# Power_Supplies.net
KiCad netlist of a schematic drawn in Altium Designer
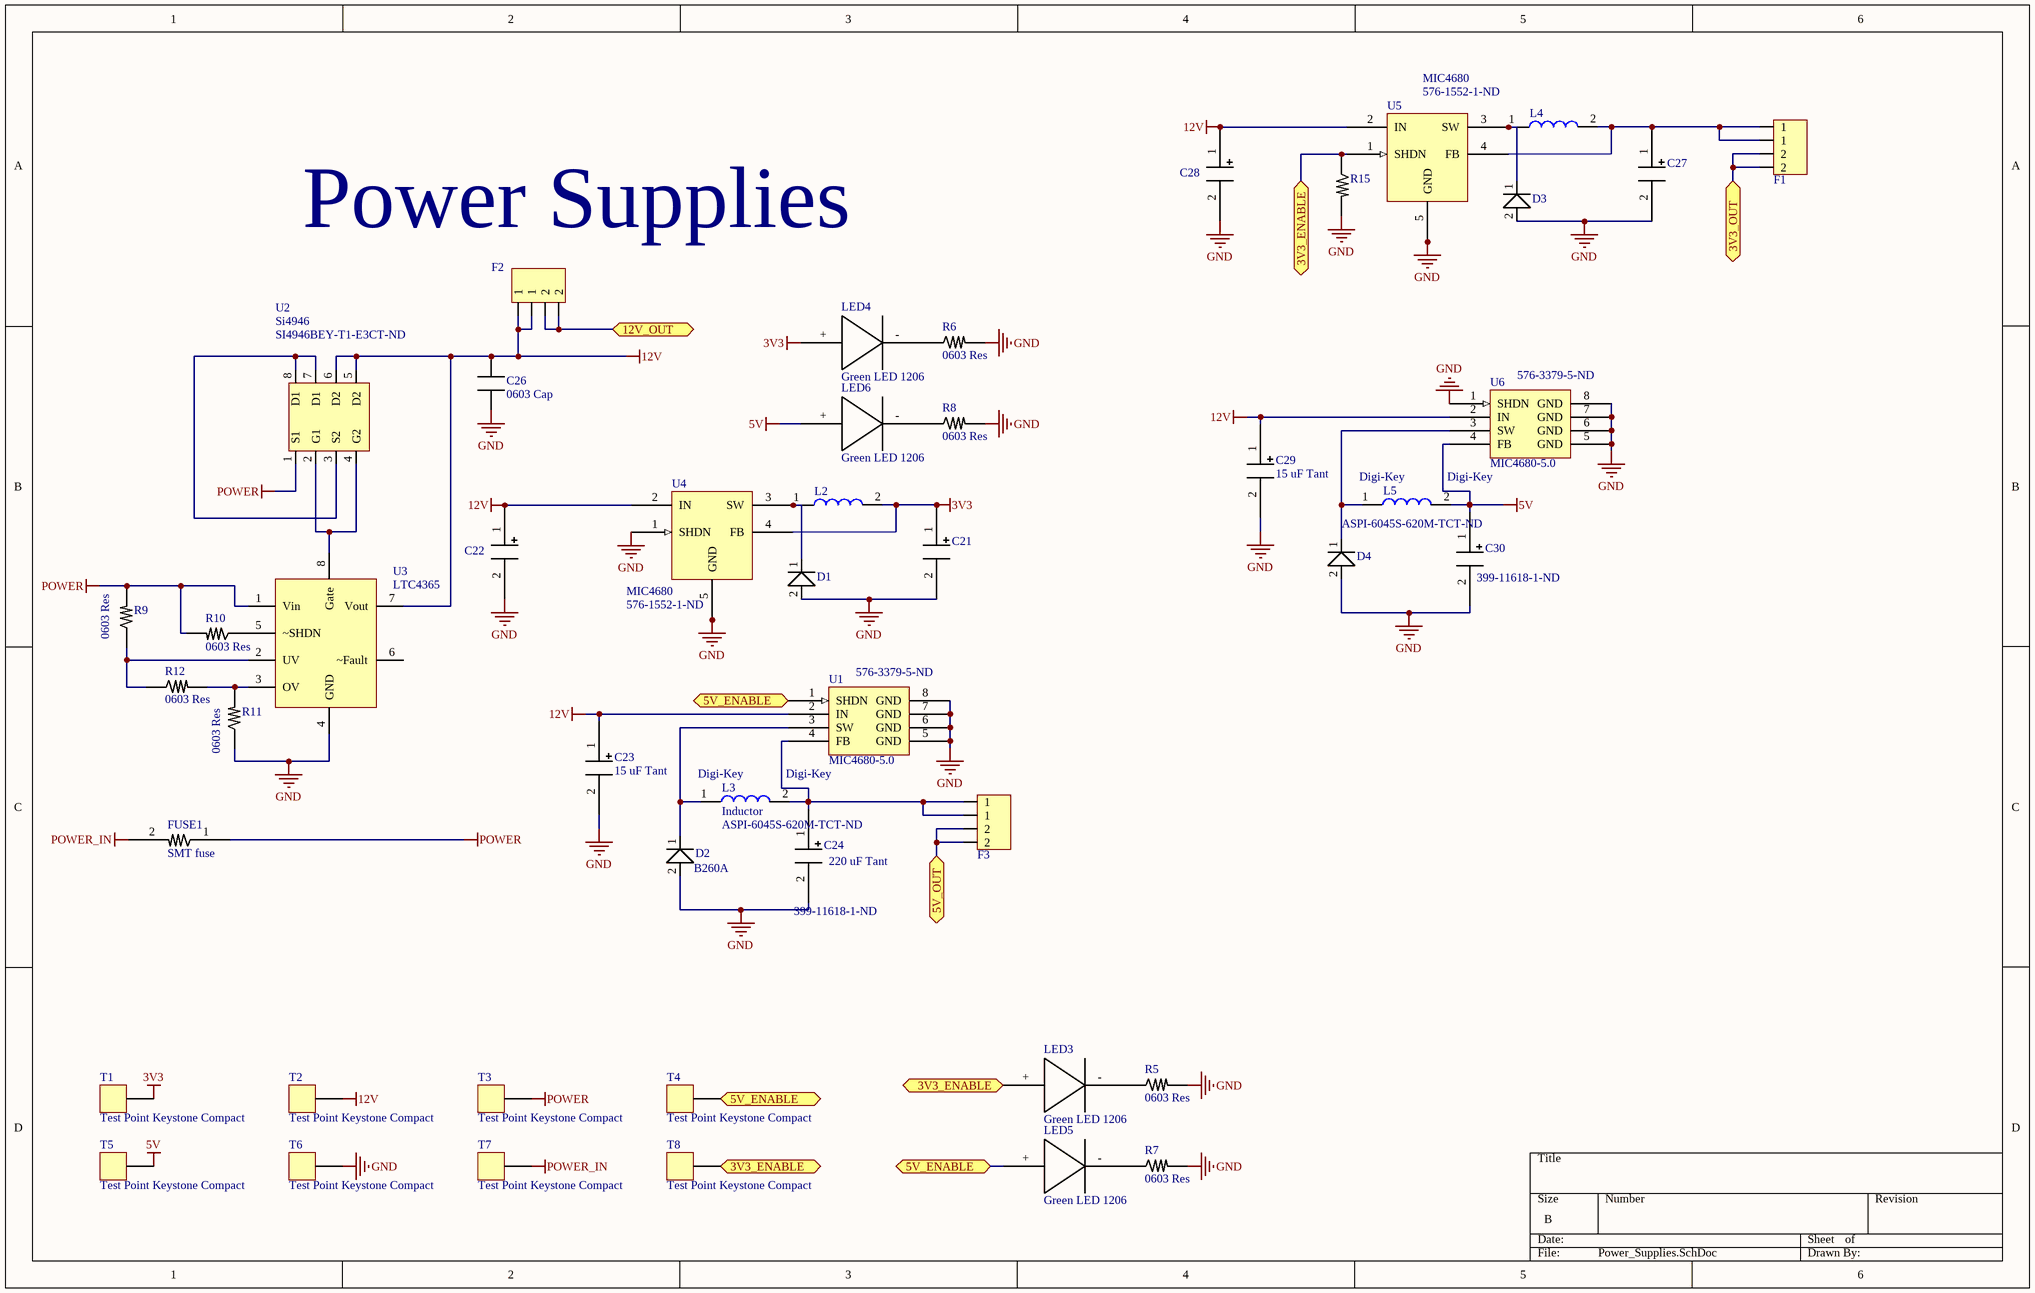
[diagram p0: Power_Supplies.SchDoc]

(export (version "E")
  (design (tool "Eeschema 10.0.6"))
  (components
    (comp (ref "C21")
      (value "220 uF Tantalum Capacitor")
      (footprint "2312 Surface Mount (POLAR)")
      (description "2312 Surface Mount Capacitor")
      (libsource (lib "CUBAJA") (part "220 uF Tantalum Capacitor"))
    )
    (comp (ref "C22")
      (value "15 uF Tantalum Capacitor")
      (footprint "1206 (POLAR)")
      (description "1206 Surface Mount Capacitor")
      (libsource (lib "CUBAJA") (part "15 uF Tantalum Capacitor"))
    )
    (comp (ref "C23")
      (value "15 uF Tant")
      (footprint "1206 (POLAR)")
      (description "1206 Surface Mount Capacitor")
      (libsource (lib "capacitors") (part "15 uF Tantalum Capacitor"))
    )
    (comp (ref "C24")
      (value "220 uF Tant")
      (footprint "2312 Surface Mount (POLAR)")
      (description "2312 Surface Mount Capacitor")
      (fields (field (name "SUPPLIER PART NUMBER 1") "399-11618-1-ND"))
      (libsource (lib "capacitors") (part "220 uF Tantalum Capacitor"))
    )
    (comp (ref "C26")
      (value "0603 Cap")
      (footprint "0603/1608 SMD Resistor")
      (description "100 uF electrolytic cap")
      (libsource (lib "BajaIntegrated") (part "0603 Cap"))
    )
    (comp (ref "C27")
      (value "220 uF Tantalum Capacitor")
      (footprint "2312 Surface Mount (POLAR)")
      (description "2312 Surface Mount Capacitor")
      (libsource (lib "CUBAJA") (part "220 uF Tantalum Capacitor"))
    )
    (comp (ref "C28")
      (value "15 uF Tantalum Capacitor")
      (footprint "1206 (POLAR)")
      (description "1206 Surface Mount Capacitor")
      (libsource (lib "CUBAJA") (part "15 uF Tantalum Capacitor"))
    )
    (comp (ref "C29")
      (value "15 uF Tant")
      (footprint "1206 (POLAR)")
      (description "1206 Surface Mount Capacitor")
      (libsource (lib "capacitors") (part "15 uF Tantalum Capacitor"))
    )
    (comp (ref "C30")
      (value "220 uF Tant")
      (footprint "2312 Surface Mount (POLAR)")
      (description "2312 Surface Mount Capacitor")
      (fields (field (name "SUPPLIER PART NUMBER 1") "399-11618-1-ND"))
      (libsource (lib "capacitors") (part "220 uF Tantalum Capacitor"))
    )
    (comp (ref "D1")
      (value "B260A Flyback Diode")
      (footprint "DO-214AC")
      (libsource (lib "CUBAJA") (part "B260A Flyback Diode"))
    )
    (comp (ref "D2")
      (value "B260A")
      (footprint "DO-214AC")
      (libsource (lib "schottky") (part "B260A Flyback Diode"))
    )
    (comp (ref "D3")
      (value "B260A Flyback Diode")
      (footprint "DO-214AC")
      (libsource (lib "CUBAJA") (part "B260A Flyback Diode"))
    )
    (comp (ref "D4")
      (value "B260A")
      (footprint "DO-214AC")
      (libsource (lib "schottky") (part "B260A Flyback Diode"))
    )
    (comp (ref "F1")
      (value "Keystone Fuseholder")
      (footprint "Keystone Fuseholder 3568")
      (libsource (lib "CornellBajaLibrary") (part "Keystone Fuseholder"))
    )
    (comp (ref "F2")
      (value "Keystone Fuseholder")
      (footprint "Keystone Fuseholder 3568")
      (libsource (lib "") (part "Keystone Fuseholder_1"))
    )
    (comp (ref "F3")
      (value "Keystone Fuseholder")
      (footprint "Keystone Fuseholder 3568")
      (libsource (lib "CornellBajaLibrary") (part "Keystone Fuseholder"))
    )
    (comp (ref "FUSE1")
      (value "SMT fuse")
      (footprint "1206")
      (description "0 ohm surface mount resistor.")
      (libsource (lib "Integrated_Library") (part "0 Resistor Surface mount 1206"))
    )
    (comp (ref "L2")
      (value "ASPI-6045S")
      (footprint "ASPI-6045")
      (description "68 uH 1.2A surface mount inductor")
      (libsource (lib "CUBAJA") (part "ASPI-6045S"))
    )
    (comp (ref "L3")
      (value "Inductor")
      (footprint "ASPI-6045")
      (fields
        (field (name "SUPPLIER 1") "Digi-Key")
        (field (name "SUPPLIER PART NUMBER 1") "ASPI-6045S-620M-TCT-ND")
      )
      (libsource (lib "CornellBajaLibrary") (part "Inductor"))
    )
    (comp (ref "L4")
      (value "ASPI-6045S")
      (footprint "ASPI-6045")
      (description "68 uH 1.2A surface mount inductor")
      (libsource (lib "CUBAJA") (part "ASPI-6045S"))
    )
    (comp (ref "L5")
      (value "Inductor")
      (footprint "ASPI-6045")
      (fields
        (field (name "SUPPLIER 1") "Digi-Key")
        (field (name "SUPPLIER PART NUMBER 1") "ASPI-6045S-620M-TCT-ND")
      )
      (libsource (lib "CornellBajaLibrary") (part "Inductor"))
    )
    (comp (ref "LED3")
      (value "Green LED 1206")
      (footprint "Panel_Mount_LED")
      (description "Green surface mount LED")
      (libsource (lib "CUBAJA") (part "1206 Green LED"))
    )
    (comp (ref "LED4")
      (value "Green LED 1206")
      (footprint "Panel_Mount_LED")
      (description "Green surface mount LED")
      (libsource (lib "CUBAJA") (part "1206 Green LED"))
    )
    (comp (ref "LED5")
      (value "Green LED 1206")
      (footprint "Cathode Mark 1206 led footprint")
      (description "Green surface mount LED")
      (libsource (lib "CUBAJA") (part "1206 Green LED"))
    )
    (comp (ref "LED6")
      (value "Green LED 1206")
      (footprint "Cathode Mark 1206 led footprint")
      (description "Green surface mount LED")
      (libsource (lib "CUBAJA") (part "1206 Green LED"))
    )
    (comp (ref "R5")
      (value "0603 Res")
      (footprint "0603/1608 SMD Resistor")
      (libsource (lib "CornellBajaLibrary") (part "0603 Res"))
    )
    (comp (ref "R6")
      (value "0603 Res")
      (footprint "0603/1608 SMD Resistor")
      (libsource (lib "CornellBajaLibrary") (part "0603 Res"))
    )
    (comp (ref "R7")
      (value "0603 Res")
      (footprint "0603/1608 SMD Resistor")
      (libsource (lib "CornellBajaLibrary") (part "0603 Res"))
    )
    (comp (ref "R8")
      (value "0603 Res")
      (footprint "0603/1608 SMD Resistor")
      (libsource (lib "CornellBajaLibrary") (part "0603 Res"))
    )
    (comp (ref "R9")
      (value "0603 Res")
      (footprint "0603/1608 SMD Resistor")
      (description "6.04 MOhm Res")
      (libsource (lib "BajaIntegrated") (part "0603 Res"))
    )
    (comp (ref "R10")
      (value "0603 Res")
      (footprint "0603/1608 SMD Resistor")
      (description "100 kOhm SMD Res")
      (libsource (lib "BajaIntegrated") (part "0603 Res"))
    )
    (comp (ref "R11")
      (value "0603 Res")
      (footprint "0603/1608 SMD Resistor")
      (description "210 kOhm Res")
      (libsource (lib "BajaIntegrated") (part "0603 Res"))
    )
    (comp (ref "R12")
      (value "0603 Res")
      (footprint "0603/1608 SMD Resistor")
      (libsource (lib "BajaIntegrated") (part "0603 Res"))
    )
    (comp (ref "R15")
      (value "0603 Res")
      (footprint "0603/1608 SMD Resistor")
      (description "Pull Down, 1kOhm")
      (libsource (lib "BajaIntegrated") (part "0603 Res"))
    )
    (comp (ref "T1")
      (value "Test Point Keystone Compact")
      (footprint "Keystone Test Point Compact")
      (libsource (lib "CornellBajaLibrary") (part "Test Point Keystone Compact"))
    )
    (comp (ref "T2")
      (value "Test Point Keystone Compact")
      (footprint "Keystone Test Point Compact")
      (libsource (lib "CornellBajaLibrary") (part "Test Point Keystone Compact"))
    )
    (comp (ref "T3")
      (value "Test Point Keystone Compact")
      (footprint "Keystone Test Point Compact")
      (libsource (lib "CornellBajaLibrary") (part "Test Point Keystone Compact"))
    )
    (comp (ref "T4")
      (value "Test Point Keystone Compact")
      (footprint "Keystone Test Point Compact")
      (libsource (lib "CornellBajaLibrary") (part "Test Point Keystone Compact"))
    )
    (comp (ref "T5")
      (value "Test Point Keystone Compact")
      (footprint "Keystone Test Point Compact")
      (libsource (lib "CornellBajaLibrary") (part "Test Point Keystone Compact"))
    )
    (comp (ref "T6")
      (value "Test Point Keystone Compact")
      (footprint "Keystone Test Point Compact")
      (libsource (lib "CornellBajaLibrary") (part "Test Point Keystone Compact"))
    )
    (comp (ref "T7")
      (value "Test Point Keystone Compact")
      (footprint "Keystone Test Point Compact")
      (libsource (lib "CornellBajaLibrary") (part "Test Point Keystone Compact"))
    )
    (comp (ref "T8")
      (value "Test Point Keystone Compact")
      (footprint "Keystone Test Point Compact")
      (libsource (lib "CornellBajaLibrary") (part "Test Point Keystone Compact"))
    )
    (comp (ref "U1")
      (value "MIC4680-5.0")
      (footprint "SOIC8")
      (description "5V Fixed Switching Regulator 1A")
      (fields (field (name "SUPPLIER 1") "Digi-Key") (field (name "SUPPLIER PART NUMBER 1") "576-3379-5-ND"))
      (libsource (lib "regulators") (part "MIC4680-5.0"))
    )
    (comp (ref "U2")
      (value "Si4946")
      (footprint "S0-8")
      (fields (field (name "SUPPLIER PART NUMBER 1") "SI4946BEY-T1-E3CT-ND"))
      (libsource (lib "BajaIntegrated") (part "Si4946"))
    )
    (comp (ref "U3") (value "LTC4365") (footprint "TS8") (libsource (lib "BajaIntegrated") (part "LTC4365")))
    (comp (ref "U4")
      (value "MIC4680")
      (footprint "TJA1040")
      (description "3.3V Fixed Switching Regulator 1A")
      (fields (field (name "SUPPLIER PART NUMBER 1") "576-1552-1-ND"))
      (libsource (lib "CornellBajaLibrary") (part "MIC4680"))
    )
    (comp (ref "U5")
      (value "MIC4680")
      (footprint "TJA1040")
      (description "3.3V Fixed Switching Regulator 1A")
      (fields (field (name "SUPPLIER PART NUMBER 1") "576-1552-1-ND"))
      (libsource (lib "CornellBajaLibrary") (part "MIC4680"))
    )
    (comp (ref "U6")
      (value "MIC4680-5.0")
      (footprint "SOIC8")
      (description "5V Fixed Switching Regulator 1A")
      (fields (field (name "SUPPLIER 1") "Digi-Key") (field (name "SUPPLIER PART NUMBER 1") "576-3379-5-ND"))
      (libsource (lib "regulators") (part "MIC4680-5.0"))
    )
  )
  (nets
    (net (code "1") (name "/3V3_ENABLE") (class "Default")
      (node (ref "LED3") (pin "+") (pintype "passive"))
      (node (ref "R15") (pin "1") (pinfunction "1_1") (pintype "passive"))
      (node (ref "T8") (pin "1") (pinfunction "1_1") (pintype "passive"))
      (node (ref "U5") (pin "1") (pinfunction "SHDN_1") (pintype "input"))
    )
    (net (code "2") (name "/3V3_OUT") (class "Default")
      (node (ref "F1") (pin "3") (pinfunction "2_3") (pintype "passive"))
      (node (ref "F1") (pin "4") (pinfunction "2_4") (pintype "passive"))
    )
    (net (code "3") (name "/5V_ENABLE") (class "Default")
      (node (ref "LED5") (pin "+") (pintype "passive"))
      (node (ref "T4") (pin "1") (pinfunction "1_1") (pintype "passive"))
      (node (ref "U1") (pin "1") (pinfunction "SHDN_1") (pintype "input"))
    )
    (net (code "4") (name "/5V_OUT") (class "Default")
      (node (ref "F3") (pin "3") (pinfunction "2_3") (pintype "passive"))
      (node (ref "F3") (pin "4") (pinfunction "2_4") (pintype "passive"))
    )
    (net (code "5") (name "/12V_OUT") (class "Default")
      (node (ref "F2") (pin "3") (pinfunction "2_3") (pintype "passive"))
      (node (ref "F2") (pin "4") (pinfunction "2_4") (pintype "passive"))
    )
    (net (code "6") (name "3V3") (class "Default")
      (node (ref "C21") (pin "1") (pinfunction "1_1") (pintype "passive"))
      (node (ref "L2") (pin "2") (pinfunction "2_2") (pintype "passive"))
      (node (ref "LED4") (pin "+") (pintype "passive"))
      (node (ref "T1") (pin "1") (pinfunction "1_1") (pintype "passive"))
      (node (ref "U4") (pin "4") (pinfunction "FB_4") (pintype "passive"))
    )
    (net (code "7") (name "5V") (class "Default")
      (node (ref "C30") (pin "1") (pinfunction "1_1") (pintype "passive"))
      (node (ref "L5") (pin "2") (pinfunction "2_2") (pintype "passive"))
      (node (ref "LED6") (pin "+") (pintype "passive"))
      (node (ref "T5") (pin "1") (pinfunction "1_1") (pintype "passive"))
      (node (ref "U6") (pin "4") (pinfunction "FB_4") (pintype "passive"))
    )
    (net (code "8") (name "12V") (class "Default")
      (node (ref "C22") (pin "1") (pinfunction "1_1") (pintype "passive"))
      (node (ref "C23") (pin "1") (pinfunction "1_1") (pintype "passive"))
      (node (ref "C26") (pin "2") (pinfunction "2_2") (pintype "passive"))
      (node (ref "C28") (pin "1") (pinfunction "1_1") (pintype "passive"))
      (node (ref "C29") (pin "1") (pinfunction "1_1") (pintype "passive"))
      (node (ref "F2") (pin "1") (pinfunction "1_1") (pintype "passive"))
      (node (ref "F2") (pin "2") (pinfunction "1_2") (pintype "passive"))
      (node (ref "T2") (pin "1") (pinfunction "1_1") (pintype "passive"))
      (node (ref "U1") (pin "2") (pinfunction "IN_2") (pintype "passive"))
      (node (ref "U2") (pin "5") (pinfunction "D2_5") (pintype "passive"))
      (node (ref "U2") (pin "6") (pinfunction "D2_6") (pintype "passive"))
      (node (ref "U3") (pin "7") (pinfunction "Vout_7") (pintype "passive"))
      (node (ref "U4") (pin "2") (pinfunction "IN_2") (pintype "passive"))
      (node (ref "U5") (pin "2") (pinfunction "IN_2") (pintype "passive"))
      (node (ref "U6") (pin "2") (pinfunction "IN_2") (pintype "passive"))
    )
    (net (code "9") (name "GND") (class "Default")
      (node (ref "C21") (pin "2") (pinfunction "2_2") (pintype "passive"))
      (node (ref "C22") (pin "2") (pinfunction "2_2") (pintype "passive"))
      (node (ref "C23") (pin "2") (pinfunction "2_2") (pintype "passive"))
      (node (ref "C24") (pin "2") (pinfunction "2_2") (pintype "passive"))
      (node (ref "C26") (pin "1") (pinfunction "1_1") (pintype "passive"))
      (node (ref "C27") (pin "2") (pinfunction "2_2") (pintype "passive"))
      (node (ref "C28") (pin "2") (pinfunction "2_2") (pintype "passive"))
      (node (ref "C29") (pin "2") (pinfunction "2_2") (pintype "passive"))
      (node (ref "C30") (pin "2") (pinfunction "2_2") (pintype "passive"))
      (node (ref "D1") (pin "2") (pintype "passive"))
      (node (ref "D2") (pin "2") (pintype "passive"))
      (node (ref "D3") (pin "2") (pintype "passive"))
      (node (ref "D4") (pin "2") (pintype "passive"))
      (node (ref "R11") (pin "1") (pinfunction "1_1") (pintype "passive"))
      (node (ref "R15") (pin "2") (pinfunction "2_2") (pintype "passive"))
      (node (ref "R5") (pin "2") (pinfunction "2_2") (pintype "passive"))
      (node (ref "R6") (pin "2") (pinfunction "2_2") (pintype "passive"))
      (node (ref "R7") (pin "2") (pinfunction "2_2") (pintype "passive"))
      (node (ref "R8") (pin "2") (pinfunction "2_2") (pintype "passive"))
      (node (ref "T6") (pin "1") (pinfunction "1_1") (pintype "passive"))
      (node (ref "U1") (pin "5") (pinfunction "GND_5") (pintype "passive"))
      (node (ref "U1") (pin "6") (pinfunction "GND_6") (pintype "passive"))
      (node (ref "U1") (pin "7") (pinfunction "GND_7") (pintype "passive"))
      (node (ref "U1") (pin "8") (pinfunction "GND_8") (pintype "passive"))
      (node (ref "U3") (pin "4") (pinfunction "GND_4") (pintype "passive"))
      (node (ref "U4") (pin "1") (pinfunction "SHDN_1") (pintype "input"))
      (node (ref "U4") (pin "5") (pinfunction "GND_5") (pintype "passive"))
      (node (ref "U4") (pin "6") (pinfunction "6_6") (pintype "passive"))
      (node (ref "U4") (pin "7") (pinfunction "7_7") (pintype "passive"))
      (node (ref "U4") (pin "8") (pinfunction "8_8") (pintype "passive"))
      (node (ref "U5") (pin "5") (pinfunction "GND_5") (pintype "passive"))
      (node (ref "U5") (pin "6") (pinfunction "6_6") (pintype "passive"))
      (node (ref "U5") (pin "7") (pinfunction "7_7") (pintype "passive"))
      (node (ref "U5") (pin "8") (pinfunction "8_8") (pintype "passive"))
      (node (ref "U6") (pin "1") (pinfunction "SHDN_1") (pintype "input"))
      (node (ref "U6") (pin "5") (pinfunction "GND_5") (pintype "passive"))
      (node (ref "U6") (pin "6") (pinfunction "GND_6") (pintype "passive"))
      (node (ref "U6") (pin "7") (pinfunction "GND_7") (pintype "passive"))
      (node (ref "U6") (pin "8") (pinfunction "GND_8") (pintype "passive"))
    )
    (net (code "10") (name "Net-(LED3-Pad-)") (class "Default")
      (node (ref "LED3") (pin "-") (pintype "passive"))
      (node (ref "R5") (pin "1") (pinfunction "1_1") (pintype "passive"))
    )
    (net (code "11") (name "Net-(LED4-Pad-)") (class "Default")
      (node (ref "LED4") (pin "-") (pintype "passive"))
      (node (ref "R6") (pin "1") (pinfunction "1_1") (pintype "passive"))
    )
    (net (code "12") (name "Net-(LED5-Pad-)") (class "Default")
      (node (ref "LED5") (pin "-") (pintype "passive"))
      (node (ref "R7") (pin "1") (pinfunction "1_1") (pintype "passive"))
    )
    (net (code "13") (name "Net-(LED6-Pad-)") (class "Default")
      (node (ref "LED6") (pin "-") (pintype "passive"))
      (node (ref "R8") (pin "1") (pinfunction "1_1") (pintype "passive"))
    )
    (net (code "14") (name "Net-(U1-FB)") (class "Default")
      (node (ref "C24") (pin "1") (pinfunction "1_1") (pintype "passive"))
      (node (ref "F3") (pin "1") (pinfunction "1_1") (pintype "passive"))
      (node (ref "F3") (pin "2") (pinfunction "1_2") (pintype "passive"))
      (node (ref "L3") (pin "2") (pinfunction "2_2") (pintype "passive"))
      (node (ref "U1") (pin "4") (pinfunction "FB_4") (pintype "passive"))
    )
    (net (code "15") (name "Net-(U1-SW)") (class "Default")
      (node (ref "D2") (pin "1") (pintype "passive"))
      (node (ref "L3") (pin "1") (pinfunction "1_1") (pintype "passive"))
      (node (ref "U1") (pin "3") (pinfunction "SW_3") (pintype "passive"))
    )
    (net (code "16") (name "Net-(U2-G1)") (class "Default")
      (node (ref "U2") (pin "2") (pinfunction "G1_2") (pintype "passive"))
      (node (ref "U2") (pin "4") (pinfunction "G2_4") (pintype "passive"))
      (node (ref "U3") (pin "8") (pinfunction "Gate_8") (pintype "passive"))
    )
    (net (code "17") (name "Net-(U2-S2)") (class "Default")
      (node (ref "U2") (pin "3") (pinfunction "S2_3") (pintype "passive"))
      (node (ref "U2") (pin "7") (pinfunction "D1_7") (pintype "passive"))
      (node (ref "U2") (pin "8") (pinfunction "D1_8") (pintype "passive"))
    )
    (net (code "18") (name "Net-(U3-OV)") (class "Default")
      (node (ref "R11") (pin "2") (pinfunction "2_2") (pintype "passive"))
      (node (ref "R12") (pin "2") (pinfunction "2_2") (pintype "passive"))
      (node (ref "U3") (pin "3") (pinfunction "OV_3") (pintype "passive"))
    )
    (net (code "19") (name "Net-(U3-UV)") (class "Default")
      (node (ref "R12") (pin "1") (pinfunction "1_1") (pintype "passive"))
      (node (ref "R9") (pin "1") (pinfunction "1_1") (pintype "passive"))
      (node (ref "U3") (pin "2") (pinfunction "UV_2") (pintype "passive"))
    )
    (net (code "20") (name "Net-(U3-~SHDN)") (class "Default")
      (node (ref "R10") (pin "1") (pinfunction "1_1") (pintype "passive"))
      (node (ref "U3") (pin "5") (pinfunction "~SHDN_5") (pintype "passive"))
    )
    (net (code "21") (name "Net-(U4-SW)") (class "Default")
      (node (ref "D1") (pin "1") (pintype "passive"))
      (node (ref "L2") (pin "1") (pinfunction "1_1") (pintype "passive"))
      (node (ref "U4") (pin "3") (pinfunction "SW_3") (pintype "passive"))
    )
    (net (code "22") (name "Net-(U5-FB)") (class "Default")
      (node (ref "C27") (pin "1") (pinfunction "1_1") (pintype "passive"))
      (node (ref "F1") (pin "1") (pinfunction "1_1") (pintype "passive"))
      (node (ref "F1") (pin "2") (pinfunction "1_2") (pintype "passive"))
      (node (ref "L4") (pin "2") (pinfunction "2_2") (pintype "passive"))
      (node (ref "U5") (pin "4") (pinfunction "FB_4") (pintype "passive"))
    )
    (net (code "23") (name "Net-(U5-SW)") (class "Default")
      (node (ref "D3") (pin "1") (pintype "passive"))
      (node (ref "L4") (pin "1") (pinfunction "1_1") (pintype "passive"))
      (node (ref "U5") (pin "3") (pinfunction "SW_3") (pintype "passive"))
    )
    (net (code "24") (name "Net-(U6-SW)") (class "Default")
      (node (ref "D4") (pin "1") (pintype "passive"))
      (node (ref "L5") (pin "1") (pinfunction "1_1") (pintype "passive"))
      (node (ref "U6") (pin "3") (pinfunction "SW_3") (pintype "passive"))
    )
    (net (code "25") (name "POWER") (class "Default")
      (node (ref "FUSE1") (pin "1") (pinfunction "1_1") (pintype "passive"))
      (node (ref "R10") (pin "2") (pinfunction "2_2") (pintype "passive"))
      (node (ref "R9") (pin "2") (pinfunction "2_2") (pintype "passive"))
      (node (ref "T3") (pin "1") (pinfunction "1_1") (pintype "passive"))
      (node (ref "U2") (pin "1") (pinfunction "S1_1") (pintype "passive"))
      (node (ref "U3") (pin "1") (pinfunction "Vin_1") (pintype "passive"))
    )
    (net (code "26") (name "POWER_IN") (class "Default")
      (node (ref "FUSE1") (pin "2") (pinfunction "2_2") (pintype "passive"))
      (node (ref "T7") (pin "1") (pinfunction "1_1") (pintype "passive"))
    )
    (net (code "27") (name "unconnected-(U3-~Fault-Pad6)") (class "Default")
      (node (ref "U3") (pin "6") (pinfunction "~Fault_6") (pintype "passive"))
    )
  )
)
